# Power_Supply.net
KiCad netlist of a schematic drawn in Altium Designer
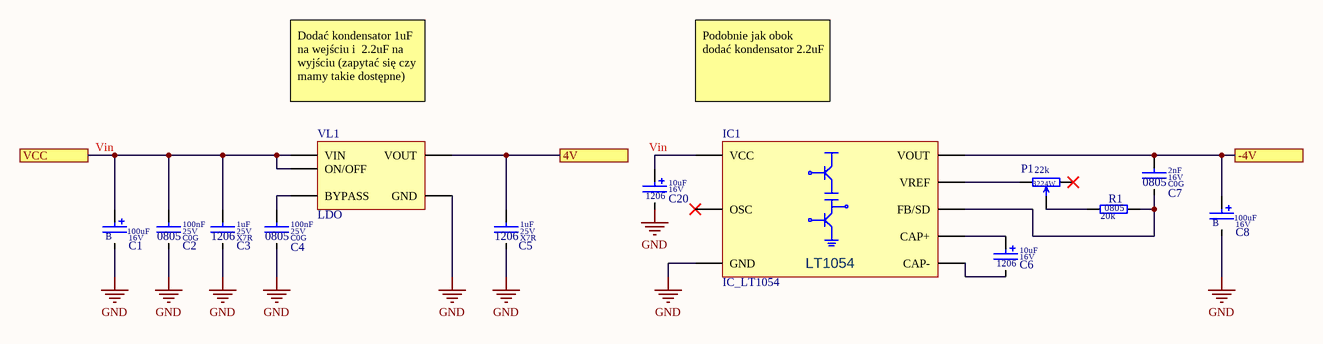
[diagram p0: Power_Supply.SchDoc]

(export (version "E")
  (design (tool "Eeschema 10.0.6"))
  (components
    (comp (ref "C1")
      (value "100uF")
      (footprint "CT_B_CASE_BIG")
      (description "Capacitor")
      (fields
        (field (name "SCH_FOOTPRINT") "B")
        (field (name "VOLTAGE") "16V")
        (field (name "Comment") "CT_Taki_jak_da_Byczek_")
      )
      (libsource (lib "SIUE_Symbol") (part "CT_Taki_jak_da_Byczek_"))
    )
    (comp (ref "C2")
      (value "100nF")
      (footprint "C_0805_2012")
      (description "Capacitor")
      (fields
        (field (name "DIELECTRIC") "C0G")
        (field (name "VOLTAGE") "25V")
        (field (name "SCH_FOOTPRINT") "0805")
        (field (name "Comment") "C_100nF_0805_C0G_25V_5")
      )
      (libsource (lib "SIUE_Symbol") (part "C_100nF_0805_C0G_25V_5"))
    )
    (comp (ref "C3")
      (value "1uF")
      (footprint "C_1206_3216")
      (description "Capacitor")
      (fields
        (field (name "DIELECTRIC") "X7R")
        (field (name "VOLTAGE") "25V")
        (field (name "SCH_FOOTPRINT") "1206")
        (field (name "Comment") "C_1uF_1206_X7R_25V_5")
      )
      (libsource (lib "SIUE_Symbol") (part "C_1uF_1206_X7R_25V_5"))
    )
    (comp (ref "C4")
      (value "100nF")
      (footprint "C_0805_2012")
      (description "Capacitor")
      (fields
        (field (name "DIELECTRIC") "C0G")
        (field (name "VOLTAGE") "25V")
        (field (name "SCH_FOOTPRINT") "0805")
        (field (name "Comment") "C_100nF_0805_C0G_25V_5")
      )
      (libsource (lib "SIUE_Symbol") (part "C_100nF_0805_C0G_25V_5"))
    )
    (comp (ref "C5")
      (value "1uF")
      (footprint "C_1206_3216")
      (description "Capacitor")
      (fields
        (field (name "DIELECTRIC") "X7R")
        (field (name "VOLTAGE") "25V")
        (field (name "SCH_FOOTPRINT") "1206")
        (field (name "Comment") "C_2.2uF_1206_X7R_25V_5")
      )
      (libsource (lib "SIUE_Symbol") (part "C_2.2uF_1206_X7R_25V_5"))
    )
    (comp (ref "C6")
      (value "10uF")
      (footprint "CT_1206_3216")
      (description "Capacitor")
      (fields
        (field (name "SCH_FOOTPRINT") "1206")
        (field (name "VOLTAGE") "16V")
        (field (name "Comment") "CT_10uF_16V_1206_10")
      )
      (libsource (lib "SIUE_Symbol") (part "CT_10uF_16V_1206_10"))
    )
    (comp (ref "C7")
      (value "2nF")
      (footprint "C_0805_2012")
      (description "Capacitor")
      (fields
        (field (name "DIELECTRIC") "C0G")
        (field (name "VOLTAGE") "16V")
        (field (name "SCH_FOOTPRINT") "0805")
        (field (name "Comment") "C_2.2nF_0805_16V_C0G_5")
      )
      (libsource (lib "SIUE_Symbol") (part "C_2.2nF_0805_16V_C0G_5"))
    )
    (comp (ref "C8")
      (value "100uF")
      (footprint "CT_B_CASE_BIG")
      (description "Capacitor")
      (fields
        (field (name "SCH_FOOTPRINT") "B")
        (field (name "VOLTAGE") "16V")
        (field (name "Comment") "CT_Taki_jak_da_Byczek_")
      )
      (libsource (lib "SIUE_Symbol") (part "CT_Taki_jak_da_Byczek_"))
    )
    (comp (ref "C20")
      (value "10uF")
      (footprint "CT_1206_3216")
      (description "Capacitor")
      (fields
        (field (name "SCH_FOOTPRINT") "1206")
        (field (name "VOLTAGE") "16V")
        (field (name "Comment") "CT_10uF_16V_1206_10")
      )
      (libsource (lib "SIUE_Symbol") (part "CT_10uF_16V_1206_10"))
    )
    (comp (ref "IC1")
      (value "IC_LT1054")
      (footprint "SOIC16")
      (libsource (lib "SIUE_Symbol") (part "IC_LT1054"))
    )
    (comp (ref "P1")
      (value "22k")
      (footprint "Potentiometer")
      (fields (field (name "SCH_FOOTPRINT") "3224W"))
      (libsource (lib "*") (part "POT"))
    )
    (comp (ref "R1")
      (value "R_20k_0805_5")
      (footprint "R_0805_2012")
      (fields
        (field (name "TOLERANCE") "5")
        (field (name "SCH_FOOTPRINT") "0805")
        (field (name "RESISTANCE") "20k")
      )
      (libsource (lib "SIUE_Symbol") (part "R_20k_0805_5"))
    )
    (comp (ref "VL1")
      (value "LDO")
      (footprint "SOT23-5")
      (libsource (lib "SIUE_Symbol") (part "VL_LP2985IM5-4.0"))
    )
  )
  (nets
    (net (code "1") (name "/-4V") (class "Default")
      (node (ref "C7") (pin "1") (pinfunction "1_1") (pintype "passive"))
      (node (ref "C8") (pin "1") (pinfunction "1_1") (pintype "passive"))
      (node (ref "IC1") (pin "11") (pinfunction "VOUT_11") (pintype "passive"))
    )
    (net (code "2") (name "/4V") (class "Default")
      (node (ref "C5") (pin "1") (pinfunction "1_1") (pintype "passive"))
      (node (ref "VL1") (pin "5") (pinfunction "VOUT_5") (pintype "passive"))
    )
    (net (code "3") (name "/Vin") (class "Default")
      (node (ref "C1") (pin "1") (pinfunction "1_1") (pintype "passive"))
      (node (ref "C2") (pin "1") (pinfunction "1_1") (pintype "passive"))
      (node (ref "C20") (pin "1") (pinfunction "1_1") (pintype "passive"))
      (node (ref "C3") (pin "1") (pinfunction "1_1") (pintype "passive"))
      (node (ref "IC1") (pin "14") (pinfunction "VCC_14") (pintype "passive"))
      (node (ref "VL1") (pin "1") (pinfunction "VIN_1") (pintype "passive"))
      (node (ref "VL1") (pin "3") (pinfunction "ON/OFF_3") (pintype "passive"))
    )
    (net (code "4") (name "GND") (class "Default")
      (node (ref "C1") (pin "2") (pinfunction "2_2") (pintype "passive"))
      (node (ref "C2") (pin "2") (pinfunction "2_2") (pintype "passive"))
      (node (ref "C20") (pin "2") (pinfunction "2_2") (pintype "passive"))
      (node (ref "C3") (pin "2") (pinfunction "2_2") (pintype "passive"))
      (node (ref "C4") (pin "2") (pinfunction "2_2") (pintype "passive"))
      (node (ref "C5") (pin "2") (pinfunction "2_2") (pintype "passive"))
      (node (ref "C8") (pin "2") (pinfunction "2_2") (pintype "passive"))
      (node (ref "IC1") (pin "5") (pinfunction "GND_5") (pintype "passive"))
      (node (ref "VL1") (pin "2") (pinfunction "GND_2") (pintype "passive"))
    )
    (net (code "5") (name "Net-(IC1-CAP+)") (class "Default")
      (node (ref "C6") (pin "1") (pinfunction "1_1") (pintype "passive"))
      (node (ref "IC1") (pin "4") (pinfunction "CAP+_4") (pintype "passive"))
    )
    (net (code "6") (name "Net-(IC1-CAP-)") (class "Default")
      (node (ref "C6") (pin "2") (pinfunction "2_2") (pintype "passive"))
      (node (ref "IC1") (pin "6") (pinfunction "CAP-_6") (pintype "passive"))
    )
    (net (code "7") (name "Net-(IC1-FB{slash}SD)") (class "Default")
      (node (ref "C7") (pin "2") (pinfunction "2_2") (pintype "passive"))
      (node (ref "IC1") (pin "3") (pinfunction "FB/SD_3") (pintype "passive"))
      (node (ref "R1") (pin "2") (pinfunction "2_2") (pintype "passive"))
    )
    (net (code "8") (name "Net-(IC1-VREF)") (class "Default")
      (node (ref "IC1") (pin "12") (pinfunction "VREF_12") (pintype "passive"))
      (node (ref "P1") (pin "3") (pinfunction "3_3") (pintype "passive"))
    )
    (net (code "9") (name "Net-(P1-Pad2)") (class "Default")
      (node (ref "P1") (pin "2") (pinfunction "2_2") (pintype "passive"))
      (node (ref "R1") (pin "1") (pinfunction "1_1") (pintype "passive"))
    )
    (net (code "10") (name "Net-(VL1-BYPASS)") (class "Default")
      (node (ref "C4") (pin "1") (pinfunction "1_1") (pintype "passive"))
      (node (ref "VL1") (pin "4") (pinfunction "BYPASS_4") (pintype "passive"))
    )
    (net (code "11") (name "unconnected-(IC1-OSC-Pad13)") (class "Default")
      (node (ref "IC1") (pin "13") (pinfunction "OSC_13") (pintype "passive+no_connect"))
    )
    (net (code "12") (name "unconnected-(P1-Pad1)") (class "Default")
      (node (ref "P1") (pin "1") (pinfunction "1_1") (pintype "passive+no_connect"))
    )
  )
)
